# B684C.net
KiCad netlist of a schematic drawn in EAGLE
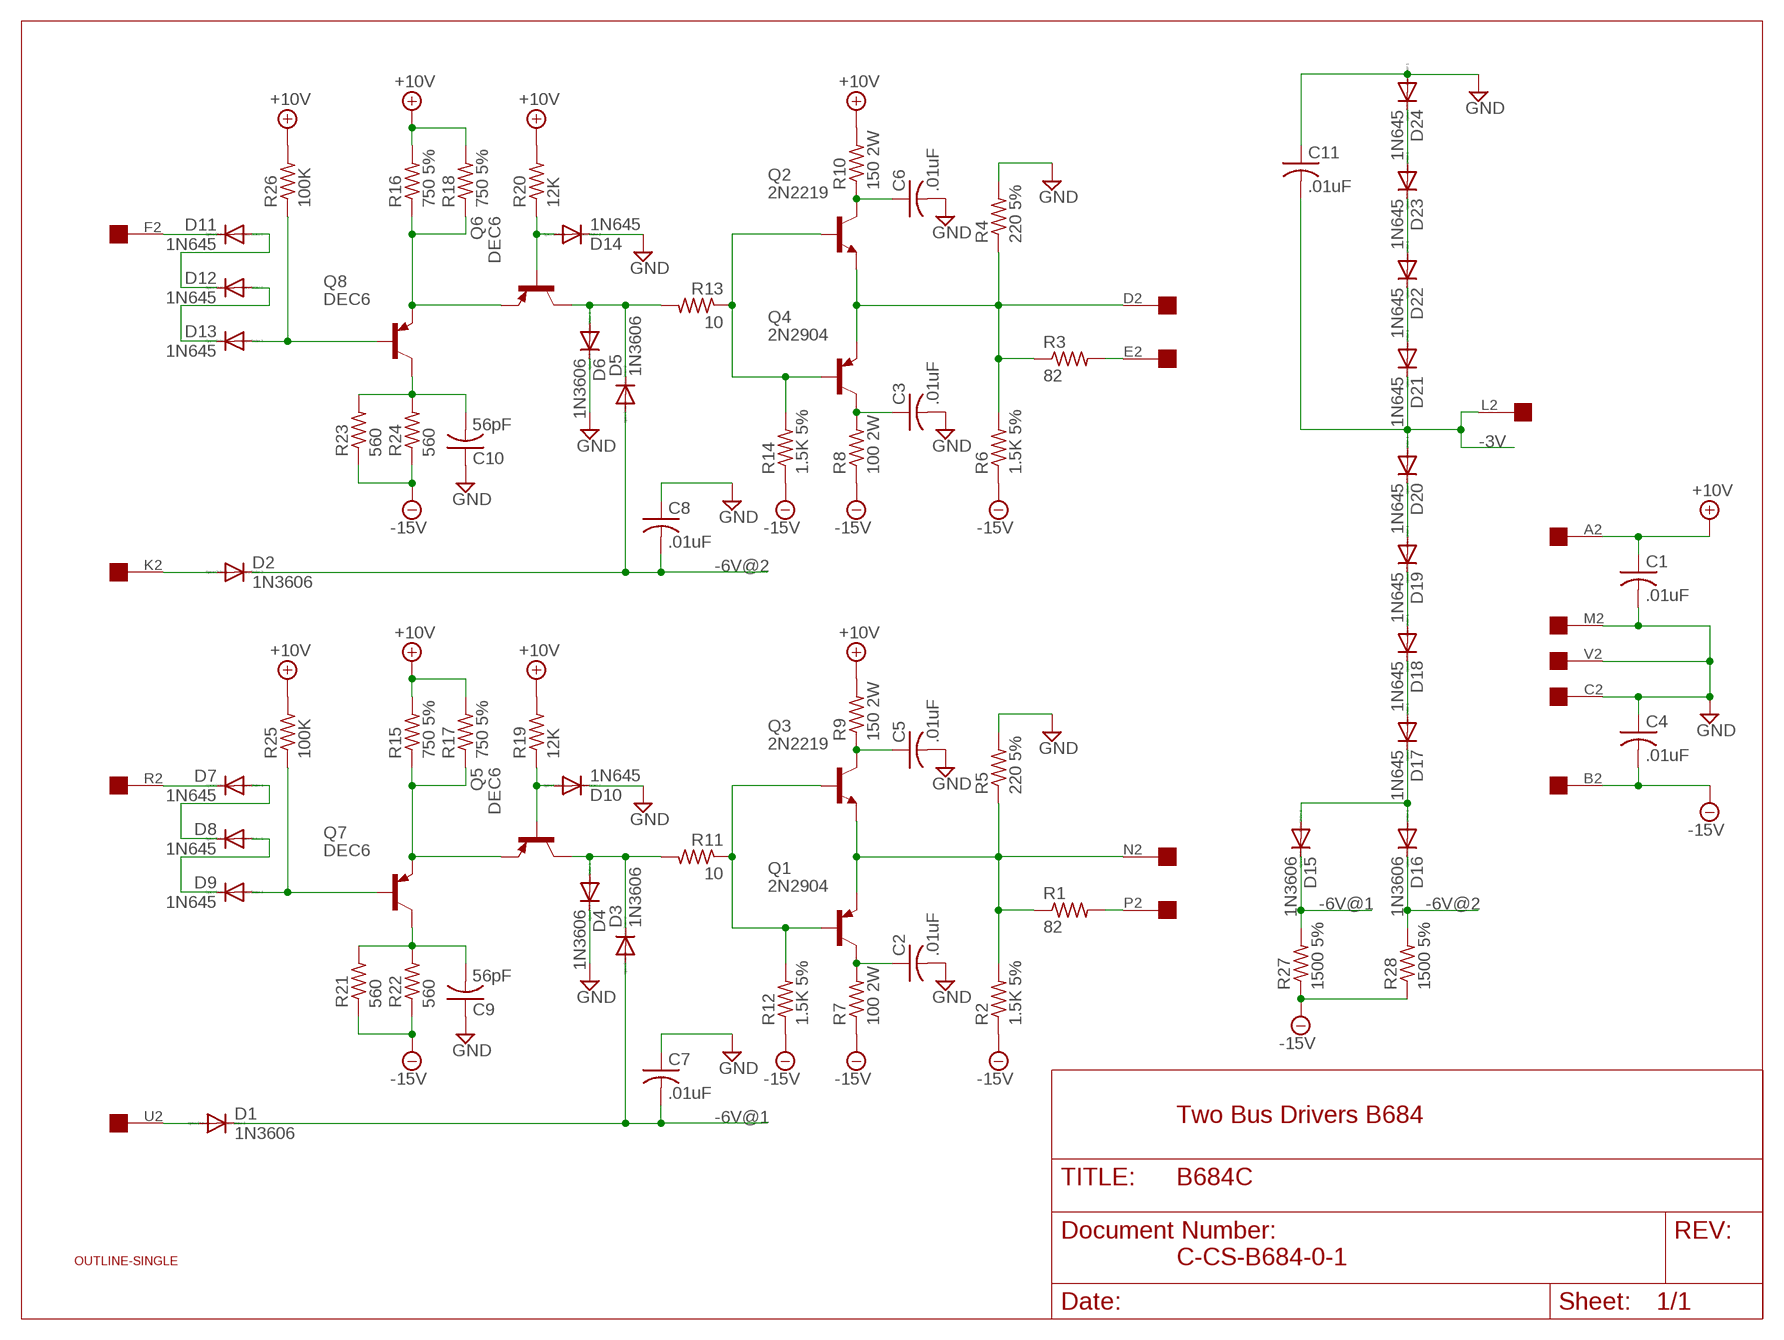
[diagram p0: schematic, sheet 1]

(export (version "E")
  (design (tool "Eeschema 10.0.6"))
  (components
    (comp (ref "C1")
      (value ".01uF")
      (footprint "eagle-import:C050-025X075")
      (libsource (lib "eagle-import") (part "C-US050-025X075"))
    )
    (comp (ref "C2")
      (value ".01uF")
      (footprint "eagle-import:C050-025X075")
      (libsource (lib "eagle-import") (part "C-US050-025X075"))
    )
    (comp (ref "C3")
      (value ".01uF")
      (footprint "eagle-import:C050-025X075")
      (libsource (lib "eagle-import") (part "C-US050-025X075"))
    )
    (comp (ref "C4")
      (value ".01uF")
      (footprint "eagle-import:C050-025X075")
      (libsource (lib "eagle-import") (part "C-US050-025X075"))
    )
    (comp (ref "C5")
      (value ".01uF")
      (footprint "eagle-import:C050-025X075")
      (libsource (lib "eagle-import") (part "C-US050-025X075"))
    )
    (comp (ref "C6")
      (value ".01uF")
      (footprint "eagle-import:C050-025X075")
      (libsource (lib "eagle-import") (part "C-US050-025X075"))
    )
    (comp (ref "C7")
      (value ".01uF")
      (footprint "eagle-import:C050-025X075")
      (libsource (lib "eagle-import") (part "C-US050-025X075"))
    )
    (comp (ref "C8")
      (value ".01uF")
      (footprint "eagle-import:C050-025X075")
      (libsource (lib "eagle-import") (part "C-US050-025X075"))
    )
    (comp (ref "C9")
      (value "56pF")
      (footprint "eagle-import:C075-032X103")
      (libsource (lib "eagle-import") (part "C-US075-032X103"))
    )
    (comp (ref "C10")
      (value "56pF")
      (footprint "eagle-import:C075-032X103")
      (libsource (lib "eagle-import") (part "C-US075-032X103"))
    )
    (comp (ref "C11")
      (value ".01uF")
      (footprint "eagle-import:C050-025X075")
      (libsource (lib "eagle-import") (part "C-US050-025X075"))
    )
    (comp (ref "D1")
      (value "1N3606")
      (footprint "eagle-import:DO35-10")
      (libsource (lib "eagle-import") (part "1N4148DO35-10"))
    )
    (comp (ref "D2")
      (value "1N3606")
      (footprint "eagle-import:DO35-10")
      (libsource (lib "eagle-import") (part "1N4148DO35-10"))
    )
    (comp (ref "D3")
      (value "1N3606")
      (footprint "eagle-import:DO35-10")
      (libsource (lib "eagle-import") (part "1N4148DO35-10"))
    )
    (comp (ref "D4")
      (value "1N3606")
      (footprint "eagle-import:DO35-10")
      (libsource (lib "eagle-import") (part "1N4148DO35-10"))
    )
    (comp (ref "D5")
      (value "1N3606")
      (footprint "eagle-import:DO35-10")
      (libsource (lib "eagle-import") (part "1N4148DO35-10"))
    )
    (comp (ref "D6")
      (value "1N3606")
      (footprint "eagle-import:DO35-10")
      (libsource (lib "eagle-import") (part "1N4148DO35-10"))
    )
    (comp (ref "D7")
      (value "1N645")
      (footprint "eagle-import:DO35-10")
      (libsource (lib "eagle-import") (part "1N4148DO35-10"))
    )
    (comp (ref "D8")
      (value "1N645")
      (footprint "eagle-import:DO35-10")
      (libsource (lib "eagle-import") (part "1N4148DO35-10"))
    )
    (comp (ref "D9")
      (value "1N645")
      (footprint "eagle-import:DO34-7")
      (libsource (lib "eagle-import") (part "DIODE-DO34-7"))
    )
    (comp (ref "D10")
      (value "1N645")
      (footprint "eagle-import:DO35-10")
      (libsource (lib "eagle-import") (part "1N4148DO35-10"))
    )
    (comp (ref "D11")
      (value "1N645")
      (footprint "eagle-import:DO35-10")
      (libsource (lib "eagle-import") (part "1N4148DO35-10"))
    )
    (comp (ref "D12")
      (value "1N645")
      (footprint "eagle-import:DO35-10")
      (libsource (lib "eagle-import") (part "1N4148DO35-10"))
    )
    (comp (ref "D13")
      (value "1N645")
      (footprint "eagle-import:DO34-7")
      (libsource (lib "eagle-import") (part "DIODE-DO34-7"))
    )
    (comp (ref "D14")
      (value "1N645")
      (footprint "eagle-import:DO35-10")
      (libsource (lib "eagle-import") (part "1N4148DO35-10"))
    )
    (comp (ref "D15")
      (value "1N3606")
      (footprint "eagle-import:DO35-10")
      (libsource (lib "eagle-import") (part "1N4148DO35-10"))
    )
    (comp (ref "D16")
      (value "1N3606")
      (footprint "eagle-import:DO35-10")
      (libsource (lib "eagle-import") (part "1N4148DO35-10"))
    )
    (comp (ref "D17")
      (value "1N645")
      (footprint "eagle-import:DO35-10")
      (libsource (lib "eagle-import") (part "1N4148DO35-10"))
    )
    (comp (ref "D18")
      (value "1N645")
      (footprint "eagle-import:DO35-10")
      (libsource (lib "eagle-import") (part "1N4148DO35-10"))
    )
    (comp (ref "D19")
      (value "1N645")
      (footprint "eagle-import:DO35-10")
      (libsource (lib "eagle-import") (part "1N4148DO35-10"))
    )
    (comp (ref "D20")
      (value "1N645")
      (footprint "eagle-import:DO35-10")
      (libsource (lib "eagle-import") (part "1N4148DO35-10"))
    )
    (comp (ref "D21")
      (value "1N645")
      (footprint "eagle-import:DO35-10")
      (libsource (lib "eagle-import") (part "1N4148DO35-10"))
    )
    (comp (ref "D22")
      (value "1N645")
      (footprint "eagle-import:DO35-10")
      (libsource (lib "eagle-import") (part "1N4148DO35-10"))
    )
    (comp (ref "D23")
      (value "1N645")
      (footprint "eagle-import:DO35-10")
      (libsource (lib "eagle-import") (part "1N4148DO35-10"))
    )
    (comp (ref "D24")
      (value "1N645")
      (footprint "eagle-import:DO35-10")
      (libsource (lib "eagle-import") (part "1N4148DO35-10"))
    )
    (comp (ref "Q1")
      (value "2N2904")
      (footprint "eagle-import:TO39")
      (libsource (lib "eagle-import") (part "2N3637"))
    )
    (comp (ref "Q2")
      (value "2N2219")
      (footprint "eagle-import:TO5")
      (libsource (lib "eagle-import") (part "2N2219"))
    )
    (comp (ref "Q3")
      (value "2N2219")
      (footprint "eagle-import:TO5")
      (libsource (lib "eagle-import") (part "2N2219"))
    )
    (comp (ref "Q4")
      (value "2N2904")
      (footprint "eagle-import:TO39")
      (libsource (lib "eagle-import") (part "2N3637"))
    )
    (comp (ref "Q5")
      (value "DEC6")
      (footprint "eagle-import:TO39")
      (libsource (lib "eagle-import") (part "2N3637"))
    )
    (comp (ref "Q6")
      (value "DEC6")
      (footprint "eagle-import:TO39")
      (libsource (lib "eagle-import") (part "2N3637"))
    )
    (comp (ref "Q7")
      (value "DEC6")
      (footprint "eagle-import:TO39")
      (libsource (lib "eagle-import") (part "2N3637"))
    )
    (comp (ref "Q8")
      (value "DEC6")
      (footprint "eagle-import:TO39")
      (libsource (lib "eagle-import") (part "2N3637"))
    )
    (comp (ref "R1")
      (value "82")
      (footprint "eagle-import:0207_10")
      (libsource (lib "eagle-import") (part "R-US_0207/10"))
    )
    (comp (ref "R2")
      (value "1.5K 5%")
      (footprint "eagle-import:0207_10")
      (libsource (lib "eagle-import") (part "R-US_0207/10"))
    )
    (comp (ref "R3")
      (value "82")
      (footprint "eagle-import:0207_10")
      (libsource (lib "eagle-import") (part "R-US_0207/10"))
    )
    (comp (ref "R4")
      (value "220 5%")
      (footprint "eagle-import:0207_10")
      (libsource (lib "eagle-import") (part "R-US_0207/10"))
    )
    (comp (ref "R5")
      (value "220 5%")
      (footprint "eagle-import:0207_10")
      (libsource (lib "eagle-import") (part "R-US_0207/10"))
    )
    (comp (ref "R6")
      (value "1.5K 5%")
      (footprint "eagle-import:0207_10")
      (libsource (lib "eagle-import") (part "R-US_0207/10"))
    )
    (comp (ref "R7")
      (value "100 2W")
      (footprint "eagle-import:P0817_22")
      (libsource (lib "eagle-import") (part "R-US_0817/22"))
    )
    (comp (ref "R8")
      (value "100 2W")
      (footprint "eagle-import:P0817_22")
      (libsource (lib "eagle-import") (part "R-US_0817/22"))
    )
    (comp (ref "R9")
      (value "150 2W")
      (footprint "eagle-import:P0817_22")
      (libsource (lib "eagle-import") (part "R-US_0817/22"))
    )
    (comp (ref "R10")
      (value "150 2W")
      (footprint "eagle-import:P0817_22")
      (libsource (lib "eagle-import") (part "R-US_0817/22"))
    )
    (comp (ref "R11")
      (value "10")
      (footprint "eagle-import:0207_10")
      (libsource (lib "eagle-import") (part "R-US_0207/10"))
    )
    (comp (ref "R12")
      (value "1.5K 5%")
      (footprint "eagle-import:0207_10")
      (libsource (lib "eagle-import") (part "R-US_0207/10"))
    )
    (comp (ref "R13")
      (value "10")
      (footprint "eagle-import:0207_10")
      (libsource (lib "eagle-import") (part "R-US_0207/10"))
    )
    (comp (ref "R14")
      (value "1.5K 5%")
      (footprint "eagle-import:0207_10")
      (libsource (lib "eagle-import") (part "R-US_0207/10"))
    )
    (comp (ref "R15")
      (value "750 5%")
      (footprint "eagle-import:0207_10")
      (libsource (lib "eagle-import") (part "R-US_0207/10"))
    )
    (comp (ref "R16")
      (value "750 5%")
      (footprint "eagle-import:0207_10")
      (libsource (lib "eagle-import") (part "R-US_0207/10"))
    )
    (comp (ref "R17")
      (value "750 5%")
      (footprint "eagle-import:0207_10")
      (libsource (lib "eagle-import") (part "R-US_0207/10"))
    )
    (comp (ref "R18")
      (value "750 5%")
      (footprint "eagle-import:0207_10")
      (libsource (lib "eagle-import") (part "R-US_0207/10"))
    )
    (comp (ref "R19")
      (value "12K")
      (footprint "eagle-import:0207_10")
      (libsource (lib "eagle-import") (part "R-US_0207/10"))
    )
    (comp (ref "R20")
      (value "12K")
      (footprint "eagle-import:0207_10")
      (libsource (lib "eagle-import") (part "R-US_0207/10"))
    )
    (comp (ref "R21")
      (value "560")
      (footprint "eagle-import:0207_10")
      (libsource (lib "eagle-import") (part "R-US_0207/10"))
    )
    (comp (ref "R22")
      (value "560")
      (footprint "eagle-import:0207_10")
      (libsource (lib "eagle-import") (part "R-US_0207/10"))
    )
    (comp (ref "R23")
      (value "560")
      (footprint "eagle-import:0207_10")
      (libsource (lib "eagle-import") (part "R-US_0207/10"))
    )
    (comp (ref "R24")
      (value "560")
      (footprint "eagle-import:0207_10")
      (libsource (lib "eagle-import") (part "R-US_0207/10"))
    )
    (comp (ref "R25")
      (value "100K")
      (footprint "eagle-import:0207_10")
      (libsource (lib "eagle-import") (part "R-US_0207/10"))
    )
    (comp (ref "R26")
      (value "100K")
      (footprint "eagle-import:0207_10")
      (libsource (lib "eagle-import") (part "R-US_0207/10"))
    )
    (comp (ref "R27")
      (value "1500 5%")
      (footprint "eagle-import:0207_10")
      (libsource (lib "eagle-import") (part "R-US_0207/10"))
    )
    (comp (ref "R28")
      (value "1500 5%")
      (footprint "eagle-import:0207_10")
      (libsource (lib "eagle-import") (part "R-US_0207/10"))
    )
    (comp (ref "U$1")
      (value "OUTLINE-SINGLE")
      (footprint "eagle-import:SINGLE")
      (libsource (lib "eagle-import") (part "OUTLINE-SINGLE"))
    )
    (comp (ref "U$2")
      (value "EDGE-1")
      (footprint "eagle-import:EDGE-CON1")
      (libsource (lib "eagle-import") (part "EDGE-1"))
    )
  )
  (nets
    (net (code "1") (name "+10V") (class "Default")
      (node (ref "C1") (pin "1") (pinfunction "1_1") (pintype "passive"))
      (node (ref "R10") (pin "2") (pinfunction "2_2") (pintype "passive"))
      (node (ref "R15") (pin "2") (pinfunction "2_2") (pintype "passive"))
      (node (ref "R16") (pin "2") (pinfunction "2_2") (pintype "passive"))
      (node (ref "R17") (pin "2") (pinfunction "2_2") (pintype "passive"))
      (node (ref "R18") (pin "2") (pinfunction "2_2") (pintype "passive"))
      (node (ref "R19") (pin "2") (pinfunction "2_2") (pintype "passive"))
      (node (ref "R20") (pin "2") (pinfunction "2_2") (pintype "passive"))
      (node (ref "R25") (pin "2") (pinfunction "2_2") (pintype "passive"))
      (node (ref "R26") (pin "2") (pinfunction "2_2") (pintype "passive"))
      (node (ref "R9") (pin "2") (pinfunction "2_2") (pintype "passive"))
      (node (ref "U$2") (pin "A2") (pinfunction "1_A2") (pintype "bidirectional"))
    )
    (net (code "2") (name "-15V") (class "Default")
      (node (ref "C4") (pin "2") (pinfunction "2_2") (pintype "passive"))
      (node (ref "R12") (pin "1") (pinfunction "1_1") (pintype "passive"))
      (node (ref "R14") (pin "1") (pinfunction "1_1") (pintype "passive"))
      (node (ref "R2") (pin "1") (pinfunction "1_1") (pintype "passive"))
      (node (ref "R21") (pin "1") (pinfunction "1_1") (pintype "passive"))
      (node (ref "R22") (pin "1") (pinfunction "1_1") (pintype "passive"))
      (node (ref "R23") (pin "1") (pinfunction "1_1") (pintype "passive"))
      (node (ref "R24") (pin "1") (pinfunction "1_1") (pintype "passive"))
      (node (ref "R27") (pin "1") (pinfunction "1_1") (pintype "passive"))
      (node (ref "R28") (pin "1") (pinfunction "1_1") (pintype "passive"))
      (node (ref "R6") (pin "1") (pinfunction "1_1") (pintype "passive"))
      (node (ref "R7") (pin "1") (pinfunction "1_1") (pintype "passive"))
      (node (ref "R8") (pin "1") (pinfunction "1_1") (pintype "passive"))
      (node (ref "U$2") (pin "B2") (pinfunction "1_B2") (pintype "bidirectional"))
    )
    (net (code "3") (name "/-3V") (class "Default")
      (node (ref "C11") (pin "2") (pinfunction "2_2") (pintype "passive"))
      (node (ref "D20") (pin "A") (pinfunction "A_A") (pintype "passive"))
      (node (ref "D21") (pin "C") (pinfunction "C_C") (pintype "passive"))
      (node (ref "U$2") (pin "L2") (pinfunction "1_L2") (pintype "bidirectional"))
    )
    (net (code "4") (name "/-6V@1") (class "Default")
      (node (ref "C7") (pin "2") (pinfunction "2_2") (pintype "passive"))
      (node (ref "D1") (pin "C") (pinfunction "C_C") (pintype "passive"))
      (node (ref "D15") (pin "C") (pinfunction "C_C") (pintype "passive"))
      (node (ref "D3") (pin "A") (pinfunction "A_A") (pintype "passive"))
      (node (ref "R27") (pin "2") (pinfunction "2_2") (pintype "passive"))
    )
    (net (code "5") (name "/-6V@2") (class "Default")
      (node (ref "C8") (pin "2") (pinfunction "2_2") (pintype "passive"))
      (node (ref "D16") (pin "C") (pinfunction "C_C") (pintype "passive"))
      (node (ref "D2") (pin "C") (pinfunction "C_C") (pintype "passive"))
      (node (ref "D5") (pin "A") (pinfunction "A_A") (pintype "passive"))
      (node (ref "R28") (pin "2") (pinfunction "2_2") (pintype "passive"))
    )
    (net (code "6") (name "GND") (class "Default")
      (node (ref "C1") (pin "2") (pinfunction "2_2") (pintype "passive"))
      (node (ref "C10") (pin "1") (pinfunction "1_1") (pintype "passive"))
      (node (ref "C11") (pin "1") (pinfunction "1_1") (pintype "passive"))
      (node (ref "C2") (pin "2") (pinfunction "2_2") (pintype "passive"))
      (node (ref "C3") (pin "2") (pinfunction "2_2") (pintype "passive"))
      (node (ref "C4") (pin "1") (pinfunction "1_1") (pintype "passive"))
      (node (ref "C5") (pin "2") (pinfunction "2_2") (pintype "passive"))
      (node (ref "C6") (pin "2") (pinfunction "2_2") (pintype "passive"))
      (node (ref "C7") (pin "1") (pinfunction "1_1") (pintype "passive"))
      (node (ref "C8") (pin "1") (pinfunction "1_1") (pintype "passive"))
      (node (ref "C9") (pin "1") (pinfunction "1_1") (pintype "passive"))
      (node (ref "D10") (pin "C") (pinfunction "C_C") (pintype "passive"))
      (node (ref "D14") (pin "C") (pinfunction "C_C") (pintype "passive"))
      (node (ref "D24") (pin "A") (pinfunction "A_A") (pintype "passive"))
      (node (ref "D4") (pin "C") (pinfunction "C_C") (pintype "passive"))
      (node (ref "D6") (pin "C") (pinfunction "C_C") (pintype "passive"))
      (node (ref "R4") (pin "2") (pinfunction "2_2") (pintype "passive"))
      (node (ref "R5") (pin "2") (pinfunction "2_2") (pintype "passive"))
      (node (ref "U$2") (pin "C2") (pinfunction "1_C2") (pintype "bidirectional"))
      (node (ref "U$2") (pin "M2") (pinfunction "1_M2") (pintype "bidirectional"))
      (node (ref "U$2") (pin "V2") (pinfunction "1_V2") (pintype "bidirectional"))
    )
    (net (code "7") (name "Net-(D7-PadA)") (class "Default")
      (node (ref "D7") (pin "A") (pinfunction "A_A") (pintype "passive"))
      (node (ref "D8") (pin "C") (pinfunction "C_C") (pintype "passive"))
    )
    (net (code "8") (name "Net-(D8-PadA)") (class "Default")
      (node (ref "D8") (pin "A") (pinfunction "A_A") (pintype "passive"))
      (node (ref "D9") (pin "C") (pinfunction "C_C") (pintype "passive"))
    )
    (net (code "9") (name "Net-(D11-PadA)") (class "Default")
      (node (ref "D11") (pin "A") (pinfunction "A_A") (pintype "passive"))
      (node (ref "D12") (pin "C") (pinfunction "C_C") (pintype "passive"))
    )
    (net (code "10") (name "Net-(D12-PadA)") (class "Default")
      (node (ref "D12") (pin "A") (pinfunction "A_A") (pintype "passive"))
      (node (ref "D13") (pin "C") (pinfunction "C_C") (pintype "passive"))
    )
    (net (code "11") (name "Net-(D15-PadA)") (class "Default")
      (node (ref "D15") (pin "A") (pinfunction "A_A") (pintype "passive"))
      (node (ref "D16") (pin "A") (pinfunction "A_A") (pintype "passive"))
      (node (ref "D17") (pin "C") (pinfunction "C_C") (pintype "passive"))
    )
    (net (code "12") (name "Net-(D17-PadA)") (class "Default")
      (node (ref "D17") (pin "A") (pinfunction "A_A") (pintype "passive"))
      (node (ref "D18") (pin "C") (pinfunction "C_C") (pintype "passive"))
    )
    (net (code "13") (name "Net-(D18-PadA)") (class "Default")
      (node (ref "D18") (pin "A") (pinfunction "A_A") (pintype "passive"))
      (node (ref "D19") (pin "C") (pinfunction "C_C") (pintype "passive"))
    )
    (net (code "14") (name "Net-(D19-PadA)") (class "Default")
      (node (ref "D19") (pin "A") (pinfunction "A_A") (pintype "passive"))
      (node (ref "D20") (pin "C") (pinfunction "C_C") (pintype "passive"))
    )
    (net (code "15") (name "Net-(D21-PadA)") (class "Default")
      (node (ref "D21") (pin "A") (pinfunction "A_A") (pintype "passive"))
      (node (ref "D22") (pin "C") (pinfunction "C_C") (pintype "passive"))
    )
    (net (code "16") (name "Net-(D22-PadA)") (class "Default")
      (node (ref "D22") (pin "A") (pinfunction "A_A") (pintype "passive"))
      (node (ref "D23") (pin "C") (pinfunction "C_C") (pintype "passive"))
    )
    (net (code "17") (name "Net-(D23-PadA)") (class "Default")
      (node (ref "D23") (pin "A") (pinfunction "A_A") (pintype "passive"))
      (node (ref "D24") (pin "C") (pinfunction "C_C") (pintype "passive"))
    )
    (net (code "18") (name "Net-(Q1-B)") (class "Default")
      (node (ref "Q1") (pin "2") (pinfunction "B_2") (pintype "passive"))
      (node (ref "Q3") (pin "2") (pinfunction "B_2") (pintype "passive"))
      (node (ref "R11") (pin "1") (pinfunction "1_1") (pintype "passive"))
      (node (ref "R12") (pin "2") (pinfunction "2_2") (pintype "passive"))
    )
    (net (code "19") (name "Net-(Q1-C)") (class "Default")
      (node (ref "C2") (pin "1") (pinfunction "1_1") (pintype "passive"))
      (node (ref "Q1") (pin "3") (pinfunction "C_3") (pintype "passive"))
      (node (ref "R7") (pin "2") (pinfunction "2_2") (pintype "passive"))
    )
    (net (code "20") (name "Net-(Q1-E)") (class "Default")
      (node (ref "Q1") (pin "1") (pinfunction "E_1") (pintype "passive"))
      (node (ref "Q3") (pin "1") (pinfunction "E_1") (pintype "passive"))
      (node (ref "R1") (pin "1") (pinfunction "1_1") (pintype "passive"))
      (node (ref "R2") (pin "2") (pinfunction "2_2") (pintype "passive"))
      (node (ref "R5") (pin "1") (pinfunction "1_1") (pintype "passive"))
      (node (ref "U$2") (pin "N2") (pinfunction "1_N2") (pintype "bidirectional"))
    )
    (net (code "21") (name "Net-(Q2-B)") (class "Default")
      (node (ref "Q2") (pin "2") (pinfunction "B_2") (pintype "passive"))
      (node (ref "Q4") (pin "2") (pinfunction "B_2") (pintype "passive"))
      (node (ref "R13") (pin "1") (pinfunction "1_1") (pintype "passive"))
      (node (ref "R14") (pin "2") (pinfunction "2_2") (pintype "passive"))
    )
    (net (code "22") (name "Net-(Q2-C)") (class "Default")
      (node (ref "C6") (pin "1") (pinfunction "1_1") (pintype "passive"))
      (node (ref "Q2") (pin "3") (pinfunction "C_3") (pintype "passive"))
      (node (ref "R10") (pin "1") (pinfunction "1_1") (pintype "passive"))
    )
    (net (code "23") (name "Net-(Q2-E)") (class "Default")
      (node (ref "Q2") (pin "1") (pinfunction "E_1") (pintype "passive"))
      (node (ref "Q4") (pin "1") (pinfunction "E_1") (pintype "passive"))
      (node (ref "R3") (pin "1") (pinfunction "1_1") (pintype "passive"))
      (node (ref "R4") (pin "1") (pinfunction "1_1") (pintype "passive"))
      (node (ref "R6") (pin "2") (pinfunction "2_2") (pintype "passive"))
      (node (ref "U$2") (pin "D2") (pinfunction "1_D2") (pintype "bidirectional"))
    )
    (net (code "24") (name "Net-(Q3-C)") (class "Default")
      (node (ref "C5") (pin "1") (pinfunction "1_1") (pintype "passive"))
      (node (ref "Q3") (pin "3") (pinfunction "C_3") (pintype "passive"))
      (node (ref "R9") (pin "1") (pinfunction "1_1") (pintype "passive"))
    )
    (net (code "25") (name "Net-(Q4-C)") (class "Default")
      (node (ref "C3") (pin "1") (pinfunction "1_1") (pintype "passive"))
      (node (ref "Q4") (pin "3") (pinfunction "C_3") (pintype "passive"))
      (node (ref "R8") (pin "2") (pinfunction "2_2") (pintype "passive"))
    )
    (net (code "26") (name "Net-(Q5-B)") (class "Default")
      (node (ref "D10") (pin "A") (pinfunction "A_A") (pintype "passive"))
      (node (ref "Q5") (pin "2") (pinfunction "B_2") (pintype "passive"))
      (node (ref "R19") (pin "1") (pinfunction "1_1") (pintype "passive"))
    )
    (net (code "27") (name "Net-(Q5-C)") (class "Default")
      (node (ref "D3") (pin "C") (pinfunction "C_C") (pintype "passive"))
      (node (ref "D4") (pin "A") (pinfunction "A_A") (pintype "passive"))
      (node (ref "Q5") (pin "3") (pinfunction "C_3") (pintype "passive"))
      (node (ref "R11") (pin "2") (pinfunction "2_2") (pintype "passive"))
    )
    (net (code "28") (name "Net-(Q5-E)") (class "Default")
      (node (ref "Q5") (pin "1") (pinfunction "E_1") (pintype "passive"))
      (node (ref "Q7") (pin "1") (pinfunction "E_1") (pintype "passive"))
      (node (ref "R15") (pin "1") (pinfunction "1_1") (pintype "passive"))
      (node (ref "R17") (pin "1") (pinfunction "1_1") (pintype "passive"))
    )
    (net (code "29") (name "Net-(Q6-B)") (class "Default")
      (node (ref "D14") (pin "A") (pinfunction "A_A") (pintype "passive"))
      (node (ref "Q6") (pin "2") (pinfunction "B_2") (pintype "passive"))
      (node (ref "R20") (pin "1") (pinfunction "1_1") (pintype "passive"))
    )
    (net (code "30") (name "Net-(Q6-C)") (class "Default")
      (node (ref "D5") (pin "C") (pinfunction "C_C") (pintype "passive"))
      (node (ref "D6") (pin "A") (pinfunction "A_A") (pintype "passive"))
      (node (ref "Q6") (pin "3") (pinfunction "C_3") (pintype "passive"))
      (node (ref "R13") (pin "2") (pinfunction "2_2") (pintype "passive"))
    )
    (net (code "31") (name "Net-(Q6-E)") (class "Default")
      (node (ref "Q6") (pin "1") (pinfunction "E_1") (pintype "passive"))
      (node (ref "Q8") (pin "1") (pinfunction "E_1") (pintype "passive"))
      (node (ref "R16") (pin "1") (pinfunction "1_1") (pintype "passive"))
      (node (ref "R18") (pin "1") (pinfunction "1_1") (pintype "passive"))
    )
    (net (code "32") (name "Net-(Q7-B)") (class "Default")
      (node (ref "D9") (pin "A") (pinfunction "A_A") (pintype "passive"))
      (node (ref "Q7") (pin "2") (pinfunction "B_2") (pintype "passive"))
      (node (ref "R25") (pin "1") (pinfunction "1_1") (pintype "passive"))
    )
    (net (code "33") (name "Net-(Q7-C)") (class "Default")
      (node (ref "C9") (pin "2") (pinfunction "2_2") (pintype "passive"))
      (node (ref "Q7") (pin "3") (pinfunction "C_3") (pintype "passive"))
      (node (ref "R21") (pin "2") (pinfunction "2_2") (pintype "passive"))
      (node (ref "R22") (pin "2") (pinfunction "2_2") (pintype "passive"))
    )
    (net (code "34") (name "Net-(Q8-B)") (class "Default")
      (node (ref "D13") (pin "A") (pinfunction "A_A") (pintype "passive"))
      (node (ref "Q8") (pin "2") (pinfunction "B_2") (pintype "passive"))
      (node (ref "R26") (pin "1") (pinfunction "1_1") (pintype "passive"))
    )
    (net (code "35") (name "Net-(Q8-C)") (class "Default")
      (node (ref "C10") (pin "2") (pinfunction "2_2") (pintype "passive"))
      (node (ref "Q8") (pin "3") (pinfunction "C_3") (pintype "passive"))
      (node (ref "R23") (pin "2") (pinfunction "2_2") (pintype "passive"))
      (node (ref "R24") (pin "2") (pinfunction "2_2") (pintype "passive"))
    )
    (net (code "36") (name "Net-(U$2E-1)") (class "Default")
      (node (ref "R3") (pin "2") (pinfunction "2_2") (pintype "passive"))
      (node (ref "U$2") (pin "E2") (pinfunction "1_E2") (pintype "bidirectional"))
    )
    (net (code "37") (name "Net-(U$2F-1)") (class "Default")
      (node (ref "D11") (pin "C") (pinfunction "C_C") (pintype "passive"))
      (node (ref "U$2") (pin "F2") (pinfunction "1_F2") (pintype "bidirectional"))
    )
    (net (code "38") (name "Net-(U$2I-1)") (class "Default")
      (node (ref "D2") (pin "A") (pinfunction "A_A") (pintype "passive"))
      (node (ref "U$2") (pin "K2") (pinfunction "1_K2") (pintype "bidirectional"))
    )
    (net (code "39") (name "Net-(U$2M-1)") (class "Default")
      (node (ref "R1") (pin "2") (pinfunction "2_2") (pintype "passive"))
      (node (ref "U$2") (pin "P2") (pinfunction "1_P2") (pintype "bidirectional"))
    )
    (net (code "40") (name "Net-(U$2N-1)") (class "Default")
      (node (ref "D7") (pin "C") (pinfunction "C_C") (pintype "passive"))
      (node (ref "U$2") (pin "R2") (pinfunction "1_R2") (pintype "bidirectional"))
    )
    (net (code "41") (name "Net-(U$2Q-1)") (class "Default")
      (node (ref "D1") (pin "A") (pinfunction "A_A") (pintype "passive"))
      (node (ref "U$2") (pin "U2") (pinfunction "1_U2") (pintype "bidirectional"))
    )
  )
)
